# Fuente_ESIQUIE_2.net
KiCad netlist of a schematic drawn in EAGLE
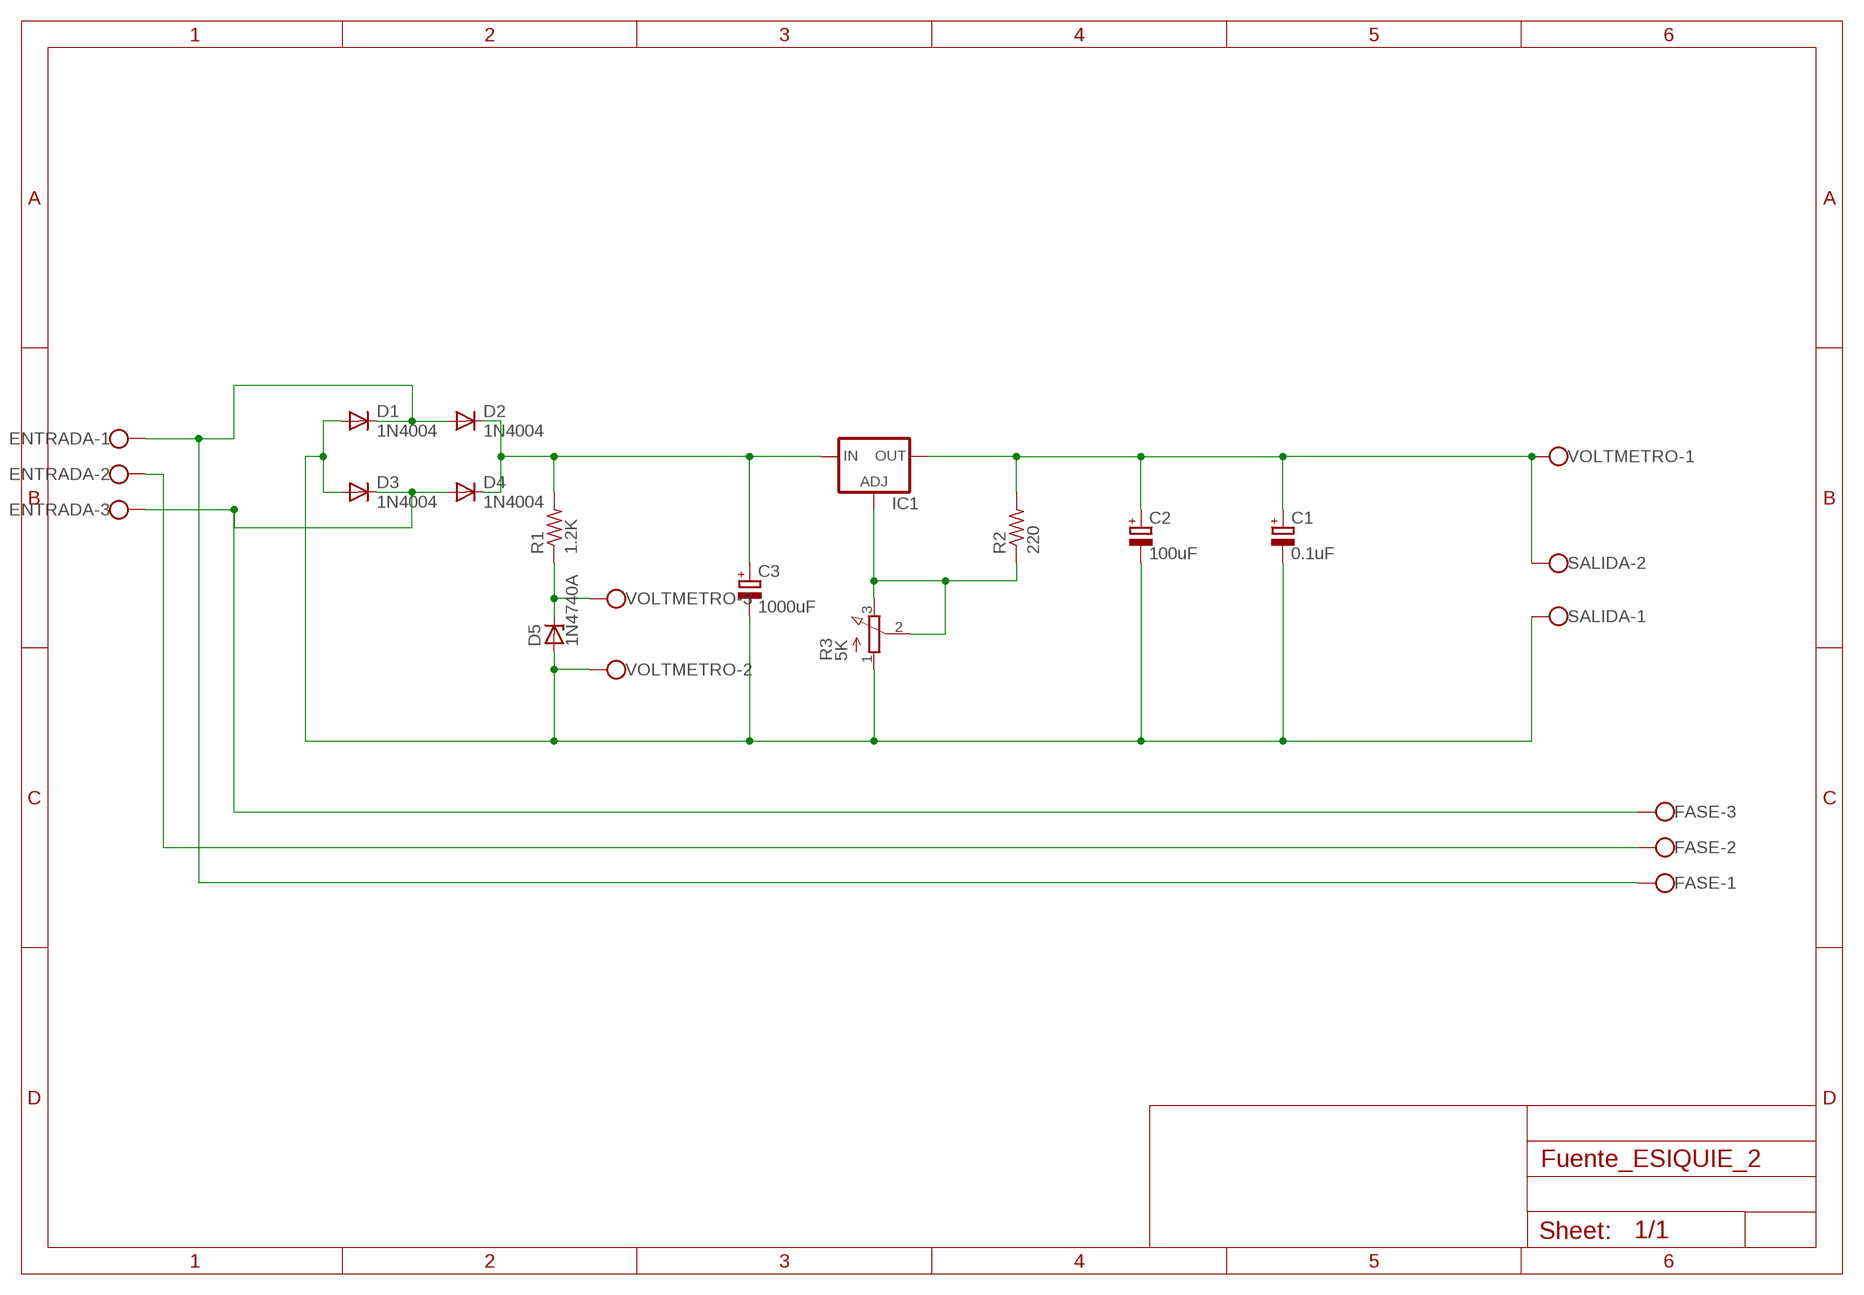
[diagram p0: schematic, sheet 1]

(export (version "E")
  (design (tool "Eeschema 10.0.6"))
  (components
    (comp (ref "C1")
      (value "0.1uF")
      (footprint "eagle-import:E3,5-8")
      (libsource (lib "eagle-import") (part "CPOL-EUE3.5-8"))
    )
    (comp (ref "C2")
      (value "100uF")
      (footprint "eagle-import:E3,5-8")
      (libsource (lib "eagle-import") (part "CPOL-EUE3.5-8"))
    )
    (comp (ref "C3")
      (value "1000uF")
      (footprint "eagle-import:E7,5-16")
      (libsource (lib "eagle-import") (part "CPOL-EUE7.5-16"))
    )
    (comp (ref "D1")
      (value "1N4004")
      (footprint "eagle-import:DO41-10")
      (libsource (lib "eagle-import") (part "1N4004"))
    )
    (comp (ref "D2")
      (value "1N4004")
      (footprint "eagle-import:DO41-10")
      (libsource (lib "eagle-import") (part "1N4004"))
    )
    (comp (ref "D3")
      (value "1N4004")
      (footprint "eagle-import:DO41-10")
      (libsource (lib "eagle-import") (part "1N4004"))
    )
    (comp (ref "D4")
      (value "1N4004")
      (footprint "eagle-import:DO41-10")
      (libsource (lib "eagle-import") (part "1N4004"))
    )
    (comp (ref "D5")
      (value "1N4740A")
      (footprint "eagle-import:DO41Z10")
      (libsource (lib "eagle-import") (part "1N4728"))
    )
    (comp (ref "ENTRADA")
      (value "W237-103")
      (footprint "eagle-import:W237-103")
      (fields (field (name "MPN") "237-103"))
      (libsource (lib "eagle-import") (part "W237-103"))
    )
    (comp (ref "FASE")
      (value "W237-103")
      (footprint "eagle-import:W237-103")
      (fields (field (name "MPN") "237-103"))
      (libsource (lib "eagle-import") (part "W237-103"))
    )
    (comp (ref "IC1")
      (value "LM317TS")
      (footprint "eagle-import:317TS")
      (libsource (lib "eagle-import") (part "LM317TS"))
    )
    (comp (ref "R1")
      (value "1.2K")
      (footprint "eagle-import:0207_12")
      (libsource (lib "eagle-import") (part "R-US_0207/12"))
    )
    (comp (ref "R2")
      (value "220")
      (footprint "eagle-import:0207_12")
      (libsource (lib "eagle-import") (part "R-US_0207/12"))
    )
    (comp (ref "R3")
      (value "5K")
      (footprint "eagle-import:3RP_1610N")
      (libsource (lib "eagle-import") (part "3RP/1610N"))
    )
    (comp (ref "SALIDA")
      (value "W237-102")
      (footprint "eagle-import:W237-102")
      (fields (field (name "MPN") "237-102"))
      (libsource (lib "eagle-import") (part "W237-102"))
    )
    (comp (ref "VOLTMETRO")
      (value "W237-103")
      (footprint "eagle-import:W237-103")
      (fields (field (name "MPN") "237-103"))
      (libsource (lib "eagle-import") (part "W237-103"))
    )
  )
  (nets
    (net (code "1") (name "Net-(ENTRADAA-KL)") (class "Default")
      (node (ref "D1") (pin "C") (pinfunction "C_C") (pintype "passive"))
      (node (ref "D2") (pin "A") (pinfunction "A_A") (pintype "passive"))
      (node (ref "ENTRADA") (pin "1") (pinfunction "KL_1") (pintype "passive"))
      (node (ref "FASE") (pin "1") (pinfunction "KL_1") (pintype "passive"))
    )
    (net (code "2") (name "Net-(ENTRADAB-KL)") (class "Default")
      (node (ref "ENTRADA") (pin "2") (pinfunction "KL_2") (pintype "passive"))
      (node (ref "FASE") (pin "2") (pinfunction "KL_2") (pintype "passive"))
    )
    (net (code "3") (name "Net-(ENTRADAC-KL)") (class "Default")
      (node (ref "D3") (pin "C") (pinfunction "C_C") (pintype "passive"))
      (node (ref "D4") (pin "A") (pinfunction "A_A") (pintype "passive"))
      (node (ref "ENTRADA") (pin "3") (pinfunction "KL_3") (pintype "passive"))
      (node (ref "FASE") (pin "3") (pinfunction "KL_3") (pintype "passive"))
    )
    (net (code "4") (name "Net-(IC1-ADJ)") (class "Default")
      (node (ref "IC1") (pin "1") (pinfunction "ADJ_1") (pintype "input"))
      (node (ref "R2") (pin "1") (pinfunction "1_1") (pintype "passive"))
      (node (ref "R3") (pin "2") (pinfunction "S_2") (pintype "passive"))
      (node (ref "R3") (pin "3") (pinfunction "E_3") (pintype "passive"))
    )
    (net (code "5") (name "Net-(IC1-IN)") (class "Default")
      (node (ref "C3") (pin "+") (pinfunction "+_+") (pintype "passive"))
      (node (ref "D2") (pin "C") (pinfunction "C_C") (pintype "passive"))
      (node (ref "D4") (pin "C") (pinfunction "C_C") (pintype "passive"))
      (node (ref "IC1") (pin "3") (pinfunction "IN_3") (pintype "input"))
      (node (ref "R1") (pin "2") (pinfunction "2_2") (pintype "passive"))
    )
    (net (code "6") (name "Net-(IC1-OUT)") (class "Default")
      (node (ref "C1") (pin "+") (pinfunction "+_+") (pintype "passive"))
      (node (ref "C2") (pin "+") (pinfunction "+_+") (pintype "passive"))
      (node (ref "IC1") (pin "2") (pinfunction "OUT_2") (pintype "passive"))
      (node (ref "R2") (pin "2") (pinfunction "2_2") (pintype "passive"))
      (node (ref "SALIDA") (pin "2") (pinfunction "KL_2") (pintype "passive"))
      (node (ref "VOLTMETRO") (pin "1") (pinfunction "KL_1") (pintype "passive"))
    )
    (net (code "7") (name "Net-(R3-A)") (class "Default")
      (node (ref "C1") (pin "-") (pinfunction "-_-") (pintype "passive"))
      (node (ref "C2") (pin "-") (pinfunction "-_-") (pintype "passive"))
      (node (ref "C3") (pin "-") (pinfunction "-_-") (pintype "passive"))
      (node (ref "D1") (pin "A") (pinfunction "A_A") (pintype "passive"))
      (node (ref "D3") (pin "A") (pinfunction "A_A") (pintype "passive"))
      (node (ref "D5") (pin "A") (pinfunction "A_A") (pintype "passive"))
      (node (ref "R3") (pin "1") (pinfunction "A_1") (pintype "passive"))
      (node (ref "SALIDA") (pin "1") (pinfunction "KL_1") (pintype "passive"))
      (node (ref "VOLTMETRO") (pin "2") (pinfunction "KL_2") (pintype "passive"))
    )
    (net (code "8") (name "Net-(VOLTMETROC-KL)") (class "Default")
      (node (ref "D5") (pin "C") (pinfunction "C_C") (pintype "passive"))
      (node (ref "R1") (pin "1") (pinfunction "1_1") (pintype "passive"))
      (node (ref "VOLTMETRO") (pin "3") (pinfunction "KL_3") (pintype "passive"))
    )
  )
)
